# OneSLiPoCharger.net
KiCad netlist of a schematic drawn in EAGLE
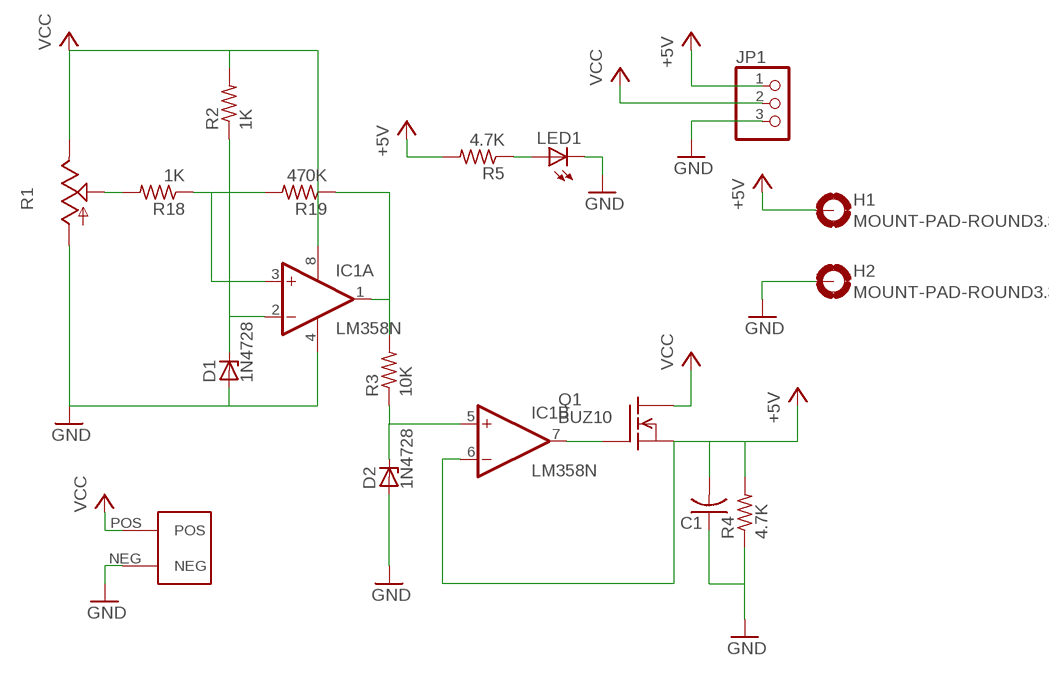
[diagram p0: schematic, sheet 1]

(export (version "E")
  (design (tool "Eeschema 10.0.6"))
  (components
    (comp (ref "C1")
      (value "C-US025-025X050")
      (footprint "eagle-import:C025-025X050")
      (libsource (lib "eagle-import") (part "C-US025-025X050"))
    )
    (comp (ref "D1")
      (value "1N4728")
      (footprint "eagle-import:DO41Z10")
      (libsource (lib "eagle-import") (part "1N4728"))
    )
    (comp (ref "D2")
      (value "1N4728")
      (footprint "eagle-import:DO41Z10")
      (libsource (lib "eagle-import") (part "1N4728"))
    )
    (comp (ref "H1")
      (value "MOUNT-PAD-ROUND3.3")
      (footprint "eagle-import:3,3-PAD")
      (libsource (lib "eagle-import") (part "MOUNT-PAD-ROUND3.3"))
    )
    (comp (ref "H2")
      (value "MOUNT-PAD-ROUND3.3")
      (footprint "eagle-import:3,3-PAD")
      (libsource (lib "eagle-import") (part "MOUNT-PAD-ROUND3.3"))
    )
    (comp (ref "IC1")
      (value "LM358N")
      (footprint "eagle-import:DIL08")
      (libsource (lib "eagle-import") (part "LM358N"))
    )
    (comp (ref "JP1")
      (value "PINHD-1X3")
      (footprint "eagle-import:1X03")
      (libsource (lib "eagle-import") (part "PINHD-1X3"))
    )
    (comp (ref "LED1")
      (value "LED3MM")
      (footprint "eagle-import:LED3MM")
      (libsource (lib "eagle-import") (part "LED3MM"))
    )
    (comp (ref "Q1")
      (value "BUZ10")
      (footprint "eagle-import:TO220")
      (libsource (lib "eagle-import") (part "BUZ10"))
    )
    (comp (ref "R1")
      (value "TRIM_US-B25P")
      (footprint "eagle-import:B25P")
      (libsource (lib "eagle-import") (part "TRIM_US-B25P"))
    )
    (comp (ref "R2")
      (value "1K")
      (footprint "eagle-import:0207_10")
      (libsource (lib "eagle-import") (part "R-US_0207/10"))
    )
    (comp (ref "R3")
      (value "10K")
      (footprint "eagle-import:0207_10")
      (libsource (lib "eagle-import") (part "R-US_0207/10"))
    )
    (comp (ref "R4")
      (value "4.7K")
      (footprint "eagle-import:0207_10")
      (libsource (lib "eagle-import") (part "R-US_0207/10"))
    )
    (comp (ref "R5")
      (value "4.7K")
      (footprint "eagle-import:0207_10")
      (libsource (lib "eagle-import") (part "R-US_0207/10"))
    )
    (comp (ref "R18")
      (value "1K")
      (footprint "eagle-import:0207_10")
      (libsource (lib "eagle-import") (part "R-US_0207/10"))
    )
    (comp (ref "R19")
      (value "470K")
      (footprint "eagle-import:0207_10")
      (libsource (lib "eagle-import") (part "R-US_0207/10"))
    )
    (comp (ref "U$3")
      (value "XT60")
      (footprint "eagle-import:XT60")
      (libsource (lib "eagle-import") (part "XT60"))
    )
  )
  (nets
    (net (code "1") (name "+5V") (class "Default")
      (node (ref "C1") (pin "2") (pinfunction "2_2") (pintype "passive"))
      (node (ref "H1") (pin "B3,3") (pinfunction "MOUNT_B3,3") (pintype "passive"))
      (node (ref "IC1") (pin "6") (pinfunction "-IN_6") (pintype "input"))
      (node (ref "JP1") (pin "1") (pinfunction "1_1") (pintype "passive"))
      (node (ref "Q1") (pin "3") (pinfunction "S_3") (pintype "passive"))
      (node (ref "R4") (pin "2") (pinfunction "2_2") (pintype "passive"))
      (node (ref "R5") (pin "2") (pinfunction "2_2") (pintype "passive"))
    )
    (net (code "2") (name "GND") (class "Default")
      (node (ref "C1") (pin "1") (pinfunction "1_1") (pintype "passive"))
      (node (ref "D1") (pin "A") (pinfunction "A_A") (pintype "passive"))
      (node (ref "D2") (pin "A") (pinfunction "A_A") (pintype "passive"))
      (node (ref "H2") (pin "B3,3") (pinfunction "MOUNT_B3,3") (pintype "passive"))
      (node (ref "IC1") (pin "4") (pinfunction "V-_4") (pintype "power_in"))
      (node (ref "JP1") (pin "3") (pinfunction "3_3") (pintype "passive"))
      (node (ref "LED1") (pin "K") (pinfunction "C_K") (pintype "passive"))
      (node (ref "R1") (pin "A") (pinfunction "A_A") (pintype "passive"))
      (node (ref "R4") (pin "1") (pinfunction "1_1") (pintype "passive"))
      (node (ref "U$3") (pin "NEG") (pinfunction "NEG_NEG") (pintype "bidirectional"))
    )
    (net (code "3") (name "Net-(IC1A-+IN)") (class "Default")
      (node (ref "IC1") (pin "3") (pinfunction "+IN_3") (pintype "input"))
      (node (ref "R18") (pin "1") (pinfunction "1_1") (pintype "passive"))
      (node (ref "R19") (pin "2") (pinfunction "2_2") (pintype "passive"))
    )
    (net (code "4") (name "Net-(IC1A--IN)") (class "Default")
      (node (ref "D1") (pin "C") (pinfunction "C_C") (pintype "passive"))
      (node (ref "IC1") (pin "2") (pinfunction "-IN_2") (pintype "input"))
      (node (ref "R2") (pin "1") (pinfunction "1_1") (pintype "passive"))
    )
    (net (code "5") (name "Net-(IC1A-OUT)") (class "Default")
      (node (ref "IC1") (pin "1") (pinfunction "OUT_1") (pintype "output"))
      (node (ref "R19") (pin "1") (pinfunction "1_1") (pintype "passive"))
      (node (ref "R3") (pin "2") (pinfunction "2_2") (pintype "passive"))
    )
    (net (code "6") (name "Net-(IC1B-+IN)") (class "Default")
      (node (ref "D2") (pin "C") (pinfunction "C_C") (pintype "passive"))
      (node (ref "IC1") (pin "5") (pinfunction "+IN_5") (pintype "input"))
      (node (ref "R3") (pin "1") (pinfunction "1_1") (pintype "passive"))
    )
    (net (code "7") (name "Net-(IC1B-OUT)") (class "Default")
      (node (ref "IC1") (pin "7") (pinfunction "OUT_7") (pintype "output"))
      (node (ref "Q1") (pin "1") (pinfunction "G_1") (pintype "passive"))
    )
    (net (code "8") (name "Net-(LED1-PadA)") (class "Default")
      (node (ref "LED1") (pin "A") (pinfunction "A_A") (pintype "passive"))
      (node (ref "R5") (pin "1") (pinfunction "1_1") (pintype "passive"))
    )
    (net (code "9") (name "Net-(R1-PadS)") (class "Default")
      (node (ref "R1") (pin "S") (pinfunction "S_S") (pintype "passive"))
      (node (ref "R18") (pin "2") (pinfunction "2_2") (pintype "passive"))
    )
    (net (code "10") (name "VCC") (class "Default")
      (node (ref "IC1") (pin "8") (pinfunction "V+_8") (pintype "power_in"))
      (node (ref "JP1") (pin "2") (pinfunction "2_2") (pintype "passive"))
      (node (ref "Q1") (pin "2") (pinfunction "D_2") (pintype "passive"))
      (node (ref "R1") (pin "E") (pinfunction "E_E") (pintype "passive"))
      (node (ref "R2") (pin "2") (pinfunction "2_2") (pintype "passive"))
      (node (ref "U$3") (pin "POS") (pinfunction "POS_POS") (pintype "bidirectional"))
    )
  )
)
